# Sheet1.net
KiCad netlist of a schematic drawn in Altium Designer
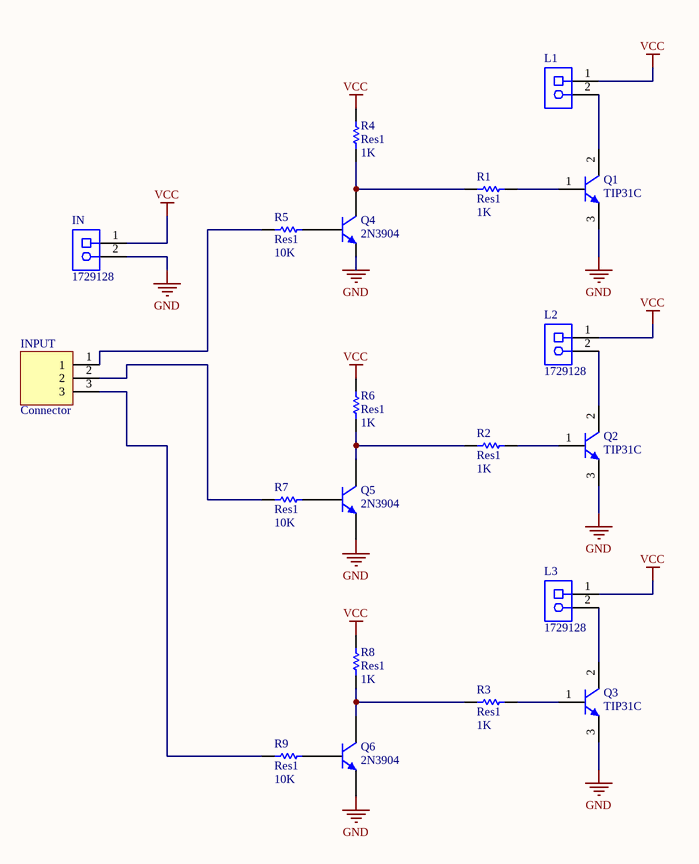
[diagram p0: Sheet1.SchDoc]

(export (version "E")
  (design (tool "Eeschema 10.0.6"))
  (components
    (comp (ref "IN")
      (value "1729128")
      (footprint "PHOE-1729128-2_V")
      (description "PCB Terminal Block, 13.5 A, 400 V, 2-Pin THD, RoHS, Bulk")
      (fields (field (name "MANUFACTURER") "Phoenix Contact"))
      (libsource (lib "Altium Content Vault") (part "CN-2P-F-R2"))
    )
    (comp (ref "INPUT")
      (value "Connector")
      (footprint "1x3x2.54 Pin Header TH V")
      (libsource (lib "CARO") (part "Header 1x3"))
    )
    (comp (ref "L1")
      (value "~")
      (footprint "PHOE-1729128-2_V")
      (description "PCB Terminal Block, 13.5 A, 400 V, 2-Pin THD, RoHS, Bulk")
      (fields (field (name "PARTNUMBER") "1729128") (field (name "MANUFACTURER") "Phoenix Contact"))
      (libsource (lib "Altium Content Vault") (part "CN-2P-F-R2"))
    )
    (comp (ref "L2")
      (value "1729128")
      (footprint "PHOE-1729128-2_V")
      (description "PCB Terminal Block, 13.5 A, 400 V, 2-Pin THD, RoHS, Bulk")
      (fields (field (name "MANUFACTURER") "Phoenix Contact"))
      (libsource (lib "Altium Content Vault") (part "CN-2P-F-R2"))
    )
    (comp (ref "L3")
      (value "1729128")
      (footprint "PHOE-1729128-2_V")
      (description "PCB Terminal Block, 13.5 A, 400 V, 2-Pin THD, RoHS, Bulk")
      (fields (field (name "MANUFACTURER") "Phoenix Contact"))
      (libsource (lib "Altium Content Vault") (part "CN-2P-F-R2"))
    )
    (comp (ref "Q1")
      (value "TIP31C")
      (footprint "ONSC-TO-220-3-221A-09")
      (description "Complementary Silicon Plastic Power Transistor, 3-Pin TO-220, Tube")
      (fields (field (name "MANUFACTURER") "On Semiconductor"))
      (libsource (lib "Altium Content Vault") (part "ONSC-NPN-B1C2E3-3_C"))
    )
    (comp (ref "Q2")
      (value "TIP31C")
      (footprint "ONSC-TO-220-3-221A-09")
      (description "Complementary Silicon Plastic Power Transistor, 3-Pin TO-220, Tube")
      (fields (field (name "MANUFACTURER") "On Semiconductor"))
      (libsource (lib "Altium Content Vault") (part "ONSC-NPN-B1C2E3-3_C"))
    )
    (comp (ref "Q3")
      (value "TIP31C")
      (footprint "ONSC-TO-220-3-221A-09")
      (description "Complementary Silicon Plastic Power Transistor, 3-Pin TO-220, Tube")
      (fields (field (name "MANUFACTURER") "On Semiconductor"))
      (libsource (lib "Altium Content Vault") (part "ONSC-NPN-B1C2E3-3_C"))
    )
    (comp (ref "Q4")
      (value "2N3904")
      (footprint "TO-92A")
      (description "NPN General Purpose Amplifier")
      (fields (field (name "PUBLISHER") "Altium Limited"))
      (libsource (lib "Miscellaneous Devices") (part "2N3904"))
    )
    (comp (ref "Q5")
      (value "2N3904")
      (footprint "TO-92A")
      (description "NPN General Purpose Amplifier")
      (fields (field (name "PUBLISHER") "Altium Limited"))
      (libsource (lib "Miscellaneous Devices") (part "2N3904"))
    )
    (comp (ref "Q6")
      (value "2N3904")
      (footprint "TO-92A")
      (description "NPN General Purpose Amplifier")
      (fields (field (name "PUBLISHER") "Altium Limited"))
      (libsource (lib "Miscellaneous Devices") (part "2N3904"))
    )
    (comp (ref "R1")
      (value "Res1")
      (footprint "AXIAL-0.3")
      (description "Resistor")
      (fields (field (name "ALTIUM_VALUE") "1K") (field (name "PUBLISHER") "Altium Limited"))
      (libsource (lib "Miscellaneous Devices") (part "Res1"))
    )
    (comp (ref "R2")
      (value "Res1")
      (footprint "AXIAL-0.3")
      (description "Resistor")
      (fields (field (name "ALTIUM_VALUE") "1K") (field (name "PUBLISHER") "Altium Limited"))
      (libsource (lib "Miscellaneous Devices") (part "Res1"))
    )
    (comp (ref "R3")
      (value "Res1")
      (footprint "AXIAL-0.3")
      (description "Resistor")
      (fields (field (name "ALTIUM_VALUE") "1K") (field (name "PUBLISHER") "Altium Limited"))
      (libsource (lib "Miscellaneous Devices") (part "Res1"))
    )
    (comp (ref "R4")
      (value "Res1")
      (footprint "AXIAL-0.3")
      (description "Resistor")
      (fields (field (name "ALTIUM_VALUE") "1K") (field (name "PUBLISHER") "Altium Limited"))
      (libsource (lib "Miscellaneous Devices") (part "Res1"))
    )
    (comp (ref "R5")
      (value "Res1")
      (footprint "AXIAL-0.3")
      (description "Resistor")
      (fields (field (name "ALTIUM_VALUE") "10K") (field (name "PUBLISHER") "Altium Limited"))
      (libsource (lib "Miscellaneous Devices") (part "Res1"))
    )
    (comp (ref "R6")
      (value "Res1")
      (footprint "AXIAL-0.3")
      (description "Resistor")
      (fields (field (name "ALTIUM_VALUE") "1K") (field (name "PUBLISHER") "Altium Limited"))
      (libsource (lib "Miscellaneous Devices") (part "Res1"))
    )
    (comp (ref "R7")
      (value "Res1")
      (footprint "AXIAL-0.3")
      (description "Resistor")
      (fields (field (name "ALTIUM_VALUE") "10K") (field (name "PUBLISHER") "Altium Limited"))
      (libsource (lib "Miscellaneous Devices") (part "Res1"))
    )
    (comp (ref "R8")
      (value "Res1")
      (footprint "AXIAL-0.3")
      (description "Resistor")
      (fields (field (name "ALTIUM_VALUE") "1K") (field (name "PUBLISHER") "Altium Limited"))
      (libsource (lib "Miscellaneous Devices") (part "Res1"))
    )
    (comp (ref "R9")
      (value "Res1")
      (footprint "AXIAL-0.3")
      (description "Resistor")
      (fields (field (name "ALTIUM_VALUE") "10K") (field (name "PUBLISHER") "Altium Limited"))
      (libsource (lib "Miscellaneous Devices") (part "Res1"))
    )
  )
  (nets
    (net (code "1") (name "GND") (class "Default")
      (node (ref "IN") (pin "2") (pinfunction "2_2") (pintype "passive"))
      (node (ref "Q1") (pin "3") (pinfunction "E_3") (pintype "passive"))
      (node (ref "Q2") (pin "3") (pinfunction "E_3") (pintype "passive"))
      (node (ref "Q3") (pin "3") (pinfunction "E_3") (pintype "passive"))
      (node (ref "Q4") (pin "1") (pinfunction "E_1") (pintype "passive"))
      (node (ref "Q5") (pin "1") (pinfunction "E_1") (pintype "passive"))
      (node (ref "Q6") (pin "1") (pinfunction "E_1") (pintype "passive"))
    )
    (net (code "2") (name "Net-(INPUT-Pad1)") (class "Default")
      (node (ref "INPUT") (pin "1") (pinfunction "1_1") (pintype "passive"))
      (node (ref "R5") (pin "1") (pinfunction "1_1") (pintype "passive"))
    )
    (net (code "3") (name "Net-(INPUT-Pad2)") (class "Default")
      (node (ref "INPUT") (pin "2") (pinfunction "2_2") (pintype "passive"))
      (node (ref "R7") (pin "1") (pinfunction "1_1") (pintype "passive"))
    )
    (net (code "4") (name "Net-(INPUT-Pad3)") (class "Default")
      (node (ref "INPUT") (pin "3") (pinfunction "3_3") (pintype "passive"))
      (node (ref "R9") (pin "1") (pinfunction "1_1") (pintype "passive"))
    )
    (net (code "5") (name "Net-(Q1-B)") (class "Default")
      (node (ref "Q1") (pin "1") (pinfunction "B_1") (pintype "passive"))
      (node (ref "R1") (pin "2") (pinfunction "2_2") (pintype "passive"))
    )
    (net (code "6") (name "Net-(Q1-C)") (class "Default")
      (node (ref "L1") (pin "2") (pinfunction "2_2") (pintype "passive"))
      (node (ref "Q1") (pin "2") (pinfunction "C_2") (pintype "passive"))
    )
    (net (code "7") (name "Net-(Q2-B)") (class "Default")
      (node (ref "Q2") (pin "1") (pinfunction "B_1") (pintype "passive"))
      (node (ref "R2") (pin "2") (pinfunction "2_2") (pintype "passive"))
    )
    (net (code "8") (name "Net-(Q2-C)") (class "Default")
      (node (ref "L2") (pin "2") (pinfunction "2_2") (pintype "passive"))
      (node (ref "Q2") (pin "2") (pinfunction "C_2") (pintype "passive"))
    )
    (net (code "9") (name "Net-(Q3-B)") (class "Default")
      (node (ref "Q3") (pin "1") (pinfunction "B_1") (pintype "passive"))
      (node (ref "R3") (pin "2") (pinfunction "2_2") (pintype "passive"))
    )
    (net (code "10") (name "Net-(Q3-C)") (class "Default")
      (node (ref "L3") (pin "2") (pinfunction "2_2") (pintype "passive"))
      (node (ref "Q3") (pin "2") (pinfunction "C_2") (pintype "passive"))
    )
    (net (code "11") (name "Net-(Q4-B)") (class "Default")
      (node (ref "Q4") (pin "2") (pinfunction "B_2") (pintype "passive"))
      (node (ref "R5") (pin "2") (pinfunction "2_2") (pintype "passive"))
    )
    (net (code "12") (name "Net-(Q4-C)") (class "Default")
      (node (ref "Q4") (pin "3") (pinfunction "C_3") (pintype "passive"))
      (node (ref "R1") (pin "1") (pinfunction "1_1") (pintype "passive"))
      (node (ref "R4") (pin "1") (pinfunction "1_1") (pintype "passive"))
    )
    (net (code "13") (name "Net-(Q5-B)") (class "Default")
      (node (ref "Q5") (pin "2") (pinfunction "B_2") (pintype "passive"))
      (node (ref "R7") (pin "2") (pinfunction "2_2") (pintype "passive"))
    )
    (net (code "14") (name "Net-(Q5-C)") (class "Default")
      (node (ref "Q5") (pin "3") (pinfunction "C_3") (pintype "passive"))
      (node (ref "R2") (pin "1") (pinfunction "1_1") (pintype "passive"))
      (node (ref "R6") (pin "1") (pinfunction "1_1") (pintype "passive"))
    )
    (net (code "15") (name "Net-(Q6-B)") (class "Default")
      (node (ref "Q6") (pin "2") (pinfunction "B_2") (pintype "passive"))
      (node (ref "R9") (pin "2") (pinfunction "2_2") (pintype "passive"))
    )
    (net (code "16") (name "Net-(Q6-C)") (class "Default")
      (node (ref "Q6") (pin "3") (pinfunction "C_3") (pintype "passive"))
      (node (ref "R3") (pin "1") (pinfunction "1_1") (pintype "passive"))
      (node (ref "R8") (pin "1") (pinfunction "1_1") (pintype "passive"))
    )
    (net (code "17") (name "VCC") (class "Default")
      (node (ref "IN") (pin "1") (pinfunction "1_1") (pintype "passive"))
      (node (ref "L1") (pin "1") (pinfunction "1_1") (pintype "passive"))
      (node (ref "L2") (pin "1") (pinfunction "1_1") (pintype "passive"))
      (node (ref "L3") (pin "1") (pinfunction "1_1") (pintype "passive"))
      (node (ref "R4") (pin "2") (pinfunction "2_2") (pintype "passive"))
      (node (ref "R6") (pin "2") (pinfunction "2_2") (pintype "passive"))
      (node (ref "R8") (pin "2") (pinfunction "2_2") (pintype "passive"))
    )
  )
)
